# Board-A_Schematics.net
KiCad netlist of a schematic drawn in Altium Designer
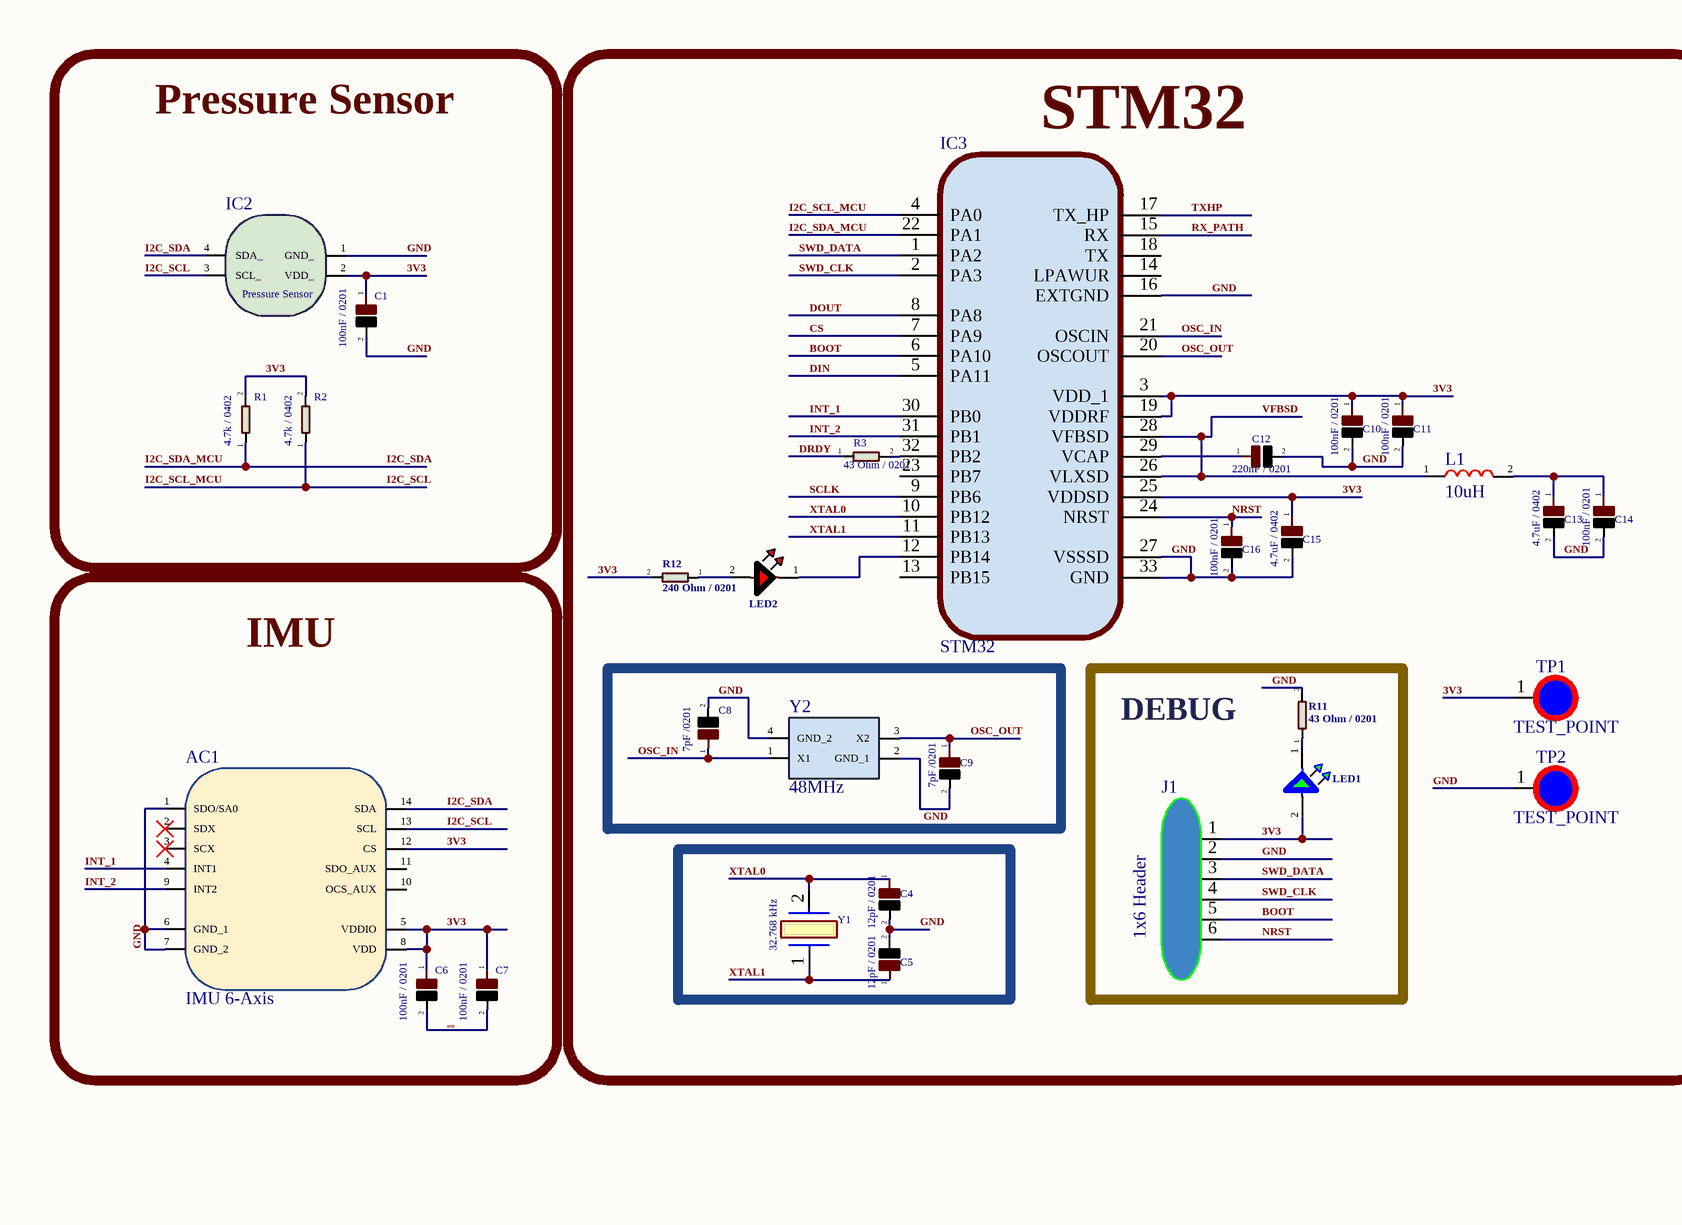
[diagram p0: Board-A_Schematics.SchDoc, left]
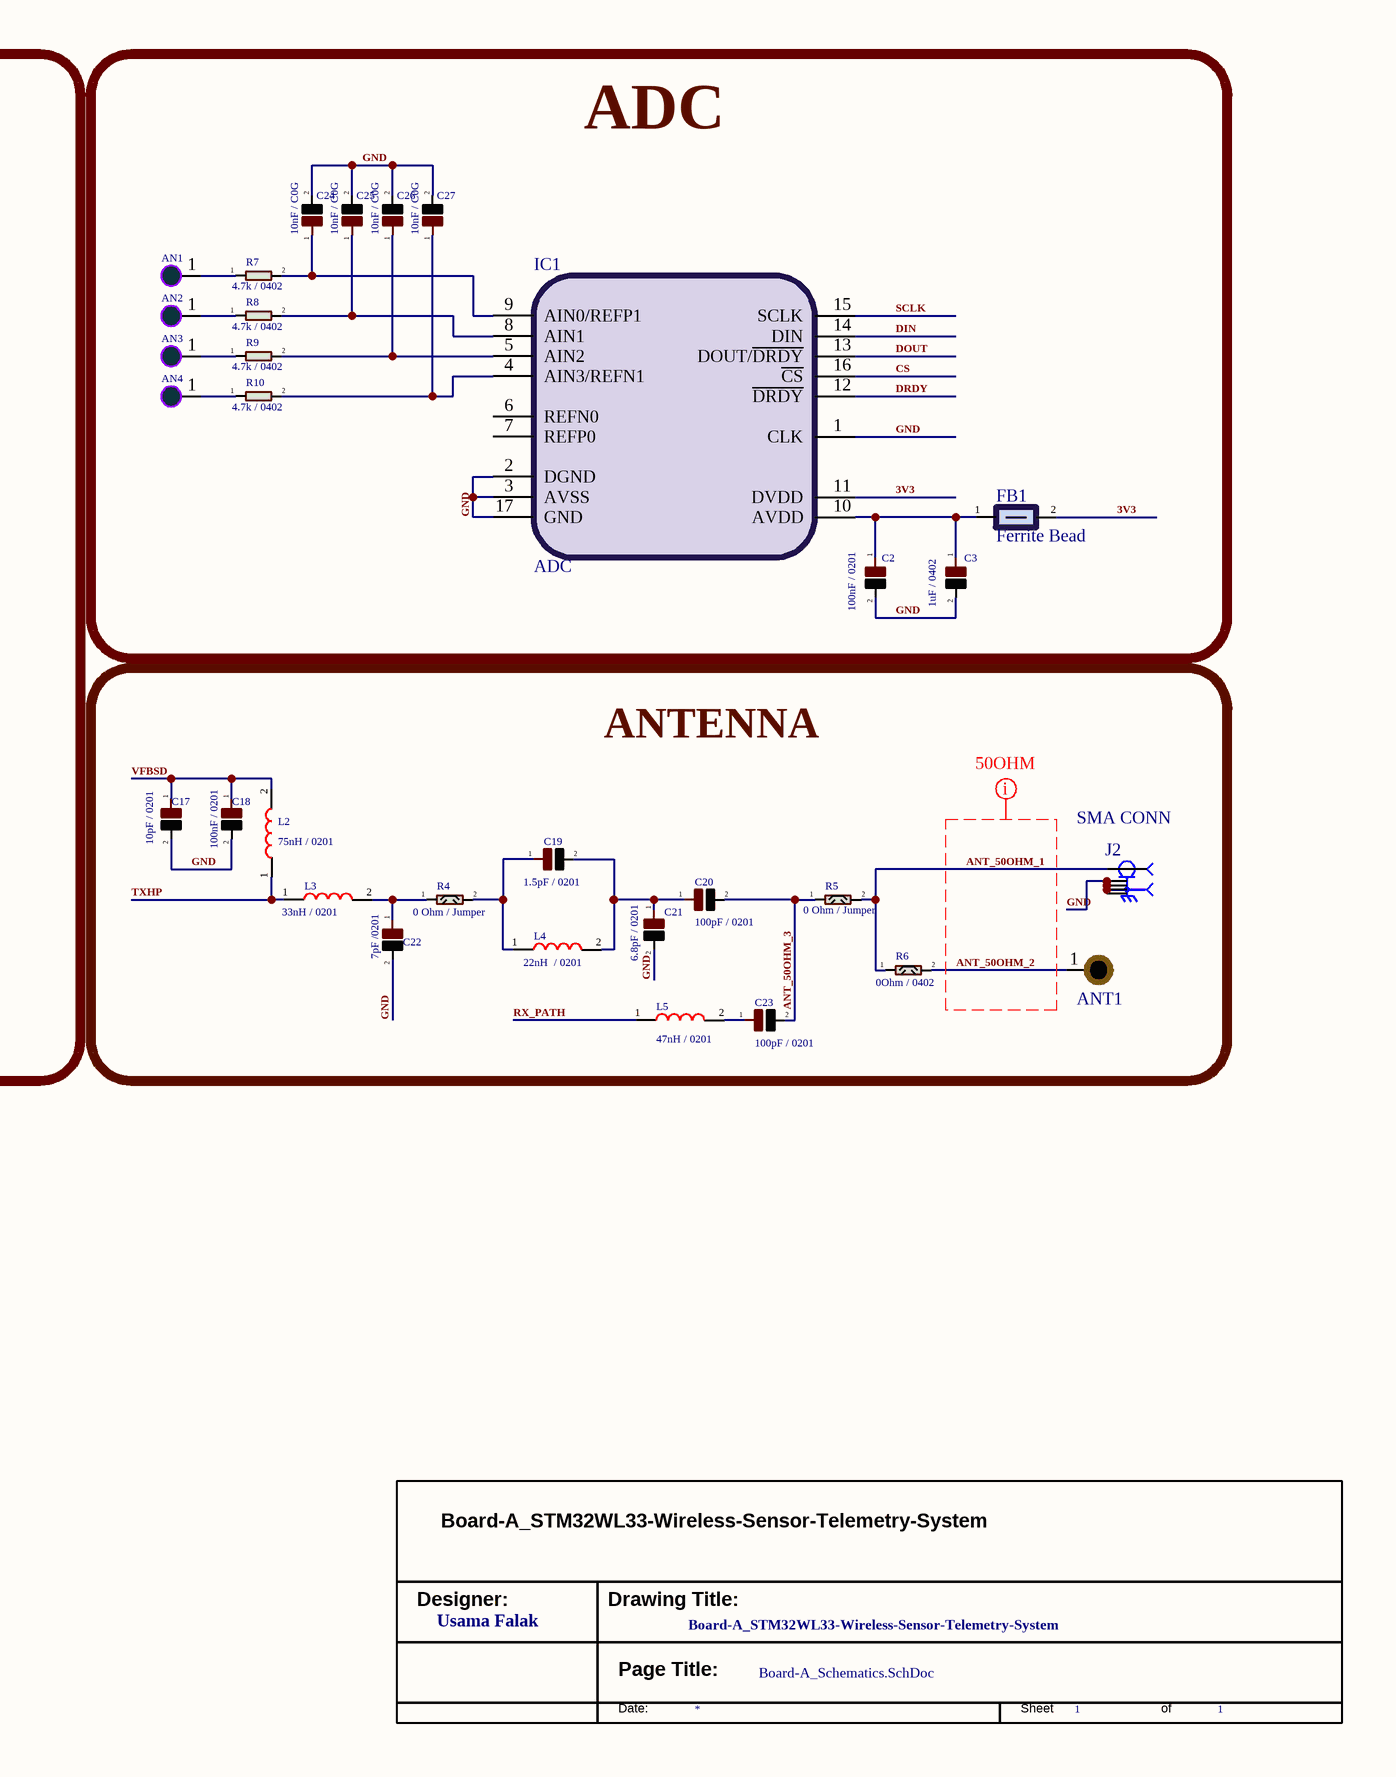
[diagram p1: Board-A_Schematics.SchDoc, right]

(export (version "E")
  (design (tool "Eeschema 10.0.6"))
  (components
    (comp (ref "*") (value "TitleBlock_MCPG_a") (libsource (lib "Sensor-SCHLIB") (part "TitleBlock_MCPG_a")))
    (comp (ref "AC1")
      (value "IMU 6-Axis")
      (footprint "Sensor-PCBLIB:LSM6DS3USTR")
      (description "Accelerometer, Gyroscope, 6 Axis Sensor I2C, SPI Output")
      (fields
        (field (name "MANUFACTURER_PART_NUMBER") "LSM6DSOTR")
        (field (name "MOUSER PART NUMBER") "511-LSM6DSOTR")
      )
      (libsource (lib "Sensor-SCHLIB") (part "LSM6DSOTR"))
    )
    (comp (ref "AN1")
      (value "ADC_AIN")
      (footprint "Analogue Pad")
      (libsource (lib "Sensor-SCHLIB") (part "ADC_PAD"))
    )
    (comp (ref "AN2")
      (value "ADC_AIN")
      (footprint "Analogue Pad")
      (libsource (lib "Sensor-SCHLIB") (part "ADC_PAD"))
    )
    (comp (ref "AN3")
      (value "ADC_AIN")
      (footprint "Analogue Pad")
      (libsource (lib "Sensor-SCHLIB") (part "ADC_PAD"))
    )
    (comp (ref "AN4")
      (value "ADC_AIN")
      (footprint "Analogue Pad")
      (libsource (lib "Sensor-SCHLIB") (part "ADC_PAD"))
    )
    (comp (ref "ANT1")
      (value "PAD")
      (footprint "ANTENNA-PAD")
      (libsource (lib "Sensor-SCHLIB") (part "ANTENNA-PAD"))
    )
    (comp (ref "C1")
      (value "100nF / 0201")
      (footprint "Sensor-PCBLIB:CAPC-C0201")
      (description "Multilayer Ceramic Capacitors MLCC - SMD/SMT 0.1 uF 16 VDC 10% 0201 X7R")
      (fields
        (field (name "MANUFACTURER_PART_NUMBER") "GRM033Z71C104KE14J")
        (field (name "MOUSER PART NUMBER") "81-GRM033Z71C104KE4J")
      )
      (libsource (lib "Sensor-SCHLIB") (part "GRM033Z71C104KE14J"))
    )
    (comp (ref "C2")
      (value "100nF / 0201")
      (footprint "Sensor-PCBLIB:CAPC-C0201")
      (description "Multilayer Ceramic Capacitors MLCC - SMD/SMT 0.1 uF 16 VDC 10% 0201 X7R")
      (fields
        (field (name "MANUFACTURER_PART_NUMBER") "GRM033Z71C104KE14J")
        (field (name "MOUSER PART NUMBER") "81-GRM033Z71C104KE4J")
      )
      (libsource (lib "Sensor-SCHLIB") (part "GRM033Z71C104KE14J"))
    )
    (comp (ref "C3")
      (value "1uF / 0402")
      (footprint "Sensor-PCBLIB:CAPC-C0402")
      (description "1uF ±10% 25V Ceramic Capacitor X6S 0402")
      (fields
        (field (name "MANUFACTURER_PART_NUMBER") "TMK105AC6105KV-F")
        (field (name "MOUSER PART NUMBER") "963-TMK105AC6105KV-F")
      )
      (libsource (lib "Sensor-SCHLIB") (part "TMK105AC6105KV-F"))
    )
    (comp (ref "C4")
      (value "12pF / 0201")
      (footprint "Sensor-PCBLIB:CAPC-C0201")
      (description "12pF ±2% 25V Ceramic Capacitor X6S 0201")
      (fields
        (field (name "MANUFACTURER_PART_NUMBER") "GJM0335C1E120GB01D")
        (field (name "MOUSER PART NUMBER") "81-GJM0335C1E120GB1D")
      )
      (libsource (lib "Sensor-SCHLIB") (part "GJM0335C1E120GB01D"))
    )
    (comp (ref "C5")
      (value "12pF / 0201")
      (footprint "Sensor-PCBLIB:CAPC-C0201")
      (description "12pF ±2% 25V Ceramic Capacitor X6S 0201")
      (fields
        (field (name "MANUFACTURER_PART_NUMBER") "GJM0335C1E120GB01D")
        (field (name "MOUSER PART NUMBER") "81-GJM0335C1E120GB1D")
      )
      (libsource (lib "") (part "GJM0335C1E120GB01D_1"))
    )
    (comp (ref "C6")
      (value "100nF / 0201")
      (footprint "Sensor-PCBLIB:CAPC-C0201")
      (description "Multilayer Ceramic Capacitors MLCC - SMD/SMT 0.1 uF 16 VDC 10% 0201 X7R")
      (fields
        (field (name "MANUFACTURER_PART_NUMBER") "GRM033Z71C104KE14J")
        (field (name "MOUSER PART NUMBER") "81-GRM033Z71C104KE4J")
      )
      (libsource (lib "Sensor-SCHLIB") (part "GRM033Z71C104KE14J"))
    )
    (comp (ref "C7")
      (value "100nF / 0201")
      (footprint "Sensor-PCBLIB:CAPC-C0201")
      (description "Multilayer Ceramic Capacitors MLCC - SMD/SMT 0.1 uF 16 VDC 10% 0201 X7R")
      (fields
        (field (name "MANUFACTURER_PART_NUMBER") "GRM033Z71C104KE14J")
        (field (name "MOUSER PART NUMBER") "81-GRM033Z71C104KE4J")
      )
      (libsource (lib "Sensor-SCHLIB") (part "GRM033Z71C104KE14J"))
    )
    (comp (ref "C8")
      (value "7pF /0201")
      (footprint "Sensor-PCBLIB:CAPC-C0201")
      (description "7pF 25V Ceramic Capacitor C0G 0201")
      (fields
        (field (name "MANUFACTURER_PART_NUMBER") "GJM0335C1E7R0BB01D")
        (field (name "LCSC-PART#") "C1864565")
      )
      (libsource (lib "Sensor-SCHLIB") (part "GJM0335C1E7R0BB01D"))
    )
    (comp (ref "C9")
      (value "7pF /0201")
      (footprint "Sensor-PCBLIB:CAPC-C0201")
      (description "7pF 25V Ceramic Capacitor C0G 0201")
      (fields
        (field (name "MANUFACTURER_PART_NUMBER") "GJM0335C1E7R0BB01D")
        (field (name "LCSC-PART#") "C1864565")
      )
      (libsource (lib "") (part "GJM0335C1E7R0BB01D_1"))
    )
    (comp (ref "C10")
      (value "100nF / 0201")
      (footprint "Sensor-PCBLIB:CAPC-C0201")
      (description "Multilayer Ceramic Capacitors MLCC - SMD/SMT 0.1 uF 16 VDC 10% 0201 X7R")
      (fields
        (field (name "MANUFACTURER_PART_NUMBER") "GRM033Z71C104KE14J")
        (field (name "MOUSER PART NUMBER") "81-GRM033Z71C104KE4J")
      )
      (libsource (lib "Sensor-SCHLIB") (part "GRM033Z71C104KE14J"))
    )
    (comp (ref "C11")
      (value "100nF / 0201")
      (footprint "Sensor-PCBLIB:CAPC-C0201")
      (description "Multilayer Ceramic Capacitors MLCC - SMD/SMT 0.1 uF 16 VDC 10% 0201 X7R")
      (fields
        (field (name "MANUFACTURER_PART_NUMBER") "GRM033Z71C104KE14J")
        (field (name "MOUSER PART NUMBER") "81-GRM033Z71C104KE4J")
      )
      (libsource (lib "Sensor-SCHLIB") (part "GRM033Z71C104KE14J"))
    )
    (comp (ref "C12")
      (value "220nF / 0201")
      (footprint "Sensor-PCBLIB:CAPC-C0201")
      (description "220nF X6S ±10% 10V 0201 Ceramic Capacitors RoHS")
      (fields
        (field (name "MANUFACTURER_PART_NUMBER") "GRM033C81A224KE01D")
        (field (name "LCSC-PART#") "C20044506")
      )
      (libsource (lib "Sensor-SCHLIB") (part "GRM033C81A224KE01D"))
    )
    (comp (ref "C13")
      (value "4.7uF / 0402")
      (footprint "Sensor-PCBLIB:CAPC-C0402")
      (description "4.7uF ±20% 25V Ceramic Capacitor 0402")
      (fields
        (field (name "MANUFACTURER_PART_NUMBER") "GRM155C61E475ME15J")
        (field (name "MOUSER PART NUMBER") "81-GRM15C61E475ME15J")
      )
      (libsource (lib "Sensor-SCHLIB") (part "GRM155C61E475ME15J"))
    )
    (comp (ref "C14")
      (value "100nF / 0201")
      (footprint "Sensor-PCBLIB:CAPC-C0201")
      (description "Multilayer Ceramic Capacitors MLCC - SMD/SMT 0.1 uF 16 VDC 10% 0201 X7R")
      (fields
        (field (name "MANUFACTURER_PART_NUMBER") "GRM033Z71C104KE14J")
        (field (name "MOUSER PART NUMBER") "81-GRM033Z71C104KE4J")
      )
      (libsource (lib "Sensor-SCHLIB") (part "GRM033Z71C104KE14J"))
    )
    (comp (ref "C15")
      (value "4.7uF / 0402")
      (footprint "Sensor-PCBLIB:CAPC-C0402")
      (description "4.7uF ±20% 25V Ceramic Capacitor 0402")
      (fields
        (field (name "MANUFACTURER_PART_NUMBER") "GRM155C61E475ME15J")
        (field (name "MOUSER PART NUMBER") "81-GRM15C61E475ME15J")
      )
      (libsource (lib "Sensor-SCHLIB") (part "GRM155C61E475ME15J"))
    )
    (comp (ref "C16")
      (value "100nF / 0201")
      (footprint "Sensor-PCBLIB:CAPC-C0201")
      (description "Multilayer Ceramic Capacitors MLCC - SMD/SMT 0.1 uF 16 VDC 10% 0201 X7R")
      (fields
        (field (name "MANUFACTURER_PART_NUMBER") "GRM033Z71C104KE14J")
        (field (name "MOUSER PART NUMBER") "81-GRM033Z71C104KE4J")
      )
      (libsource (lib "Sensor-SCHLIB") (part "GRM033Z71C104KE14J"))
    )
    (comp (ref "C17")
      (value "10pF / 0201")
      (footprint "Sensor-PCBLIB:CAPC-C0201")
      (description "10pF ±2% 25V Ceramic Capacitor C0G 0201")
      (fields
        (field (name "MANUFACTURER_PART_NUMBER") "GJM0335C1E100GB01D")
        (field (name "MOUSER PART NUMBER") "81-GJM0335C1E100GB1D")
      )
      (libsource (lib "Sensor-SCHLIB") (part "GJM0335C1E100GB01D"))
    )
    (comp (ref "C18")
      (value "100nF / 0201")
      (footprint "Sensor-PCBLIB:CAPC-C0201")
      (description "Multilayer Ceramic Capacitors MLCC - SMD/SMT 0.1 uF 16 VDC 10% 0201 X7R")
      (fields
        (field (name "MANUFACTURER_PART_NUMBER") "GRM033Z71C104KE14J")
        (field (name "MOUSER PART NUMBER") "81-GRM033Z71C104KE4J")
      )
      (libsource (lib "Sensor-SCHLIB") (part "GRM033Z71C104KE14J"))
    )
    (comp (ref "C19")
      (value "1.5pF / 0201")
      (footprint "Sensor-PCBLIB:CAPC-C0201")
      (description "1.5pF 25V Ceramic Capacitor C0G 0201")
      (fields
        (field (name "MANUFACTURER_PART_NUMBER") "GJM0335C1E1R5WB01D")
        (field (name "MOUSER PART NUMBER") "81-GJM0335C1E1R5WB1D")
      )
      (libsource (lib "Sensor-SCHLIB") (part "GJM0335C1E1R5WB01D"))
    )
    (comp (ref "C20")
      (value "100pF / 0201")
      (footprint "Sensor-PCBLIB:CAPC-C0201")
      (description "Multilayer Ceramic Capacitors MLCC - SMD/SMT 100 pF 25 VDC 1% 0201 C0G (NP0)")
      (fields
        (field (name "MANUFACTURER_PART_NUMBER") "GRM0335C1E101FA01D")
        (field (name "MOUSER PART NUMBER") "81-GRM0335C1E101FA1D")
      )
      (libsource (lib "Sensor-SCHLIB") (part "GRM0335C1E101FA01D"))
    )
    (comp (ref "C21")
      (value "6.8pF / 0201")
      (footprint "Sensor-PCBLIB:CAPC-C0201")
      (description "Multilayer Ceramic Capacitors MLCC - SMD/SMT 6.8 pF 25 VDC 0.25 pF 0201 C0G (NP0)")
      (fields
        (field (name "MANUFACTURER_PART_NUMBER") "GJM0335C1E6R8CB01D")
        (field (name "LCSC-PART#") "C415404")
      )
      (libsource (lib "Sensor-SCHLIB") (part "GJM0335C1E6R8CB01D"))
    )
    (comp (ref "C22")
      (value "7pF /0201")
      (footprint "Sensor-PCBLIB:CAPC-C0201")
      (description "7pF 25V Ceramic Capacitor C0G 0201")
      (fields
        (field (name "MANUFACTURER_PART_NUMBER") "GJM0335C1E7R0BB01D")
        (field (name "LCSC-PART#") "C1864565")
      )
      (libsource (lib "") (part "GJM0335C1E7R0BB01D_1"))
    )
    (comp (ref "C23")
      (value "100pF / 0201")
      (footprint "Sensor-PCBLIB:CAPC-C0201")
      (description "Multilayer Ceramic Capacitors MLCC - SMD/SMT 100 pF 25 VDC 1% 0201 C0G (NP0)")
      (fields
        (field (name "MANUFACTURER_PART_NUMBER") "GRM0335C1E101FA01D")
        (field (name "MOUSER PART NUMBER") "81-GRM0335C1E101FA1D")
      )
      (libsource (lib "Sensor-SCHLIB") (part "GRM0335C1E101FA01D"))
    )
    (comp (ref "C24")
      (value "10nF / C0G")
      (footprint "Sensor-PCBLIB:CAPC-C0402")
      (description "10nF ±2% 25V Ceramic Capacitor C0G 0402")
      (fields
        (field (name "MANUFACTURER_PART_NUMBER") "GRM1555C1E103GE01D")
        (field (name "MOUSER PART NUMBER") "81-GRM1555C1E103GE1D")
      )
      (libsource (lib "Sensor-SCHLIB") (part "GRM1555C1E103GE01D"))
    )
    (comp (ref "C25")
      (value "10nF / C0G")
      (footprint "Sensor-PCBLIB:CAPC-C0402")
      (description "10nF ±2% 25V Ceramic Capacitor C0G 0402")
      (fields
        (field (name "MANUFACTURER_PART_NUMBER") "GRM1555C1E103GE01D")
        (field (name "MOUSER PART NUMBER") "81-GRM1555C1E103GE1D")
      )
      (libsource (lib "Sensor-SCHLIB") (part "GRM1555C1E103GE01D"))
    )
    (comp (ref "C26")
      (value "10nF / C0G")
      (footprint "Sensor-PCBLIB:CAPC-C0402")
      (description "10nF ±2% 25V Ceramic Capacitor C0G 0402")
      (fields
        (field (name "MANUFACTURER_PART_NUMBER") "GRM1555C1E103GE01D")
        (field (name "MOUSER PART NUMBER") "81-GRM1555C1E103GE1D")
      )
      (libsource (lib "Sensor-SCHLIB") (part "GRM1555C1E103GE01D"))
    )
    (comp (ref "C27")
      (value "10nF / C0G")
      (footprint "Sensor-PCBLIB:CAPC-C0402")
      (description "10nF ±2% 25V Ceramic Capacitor C0G 0402")
      (fields
        (field (name "MANUFACTURER_PART_NUMBER") "GRM1555C1E103GE01D")
        (field (name "MOUSER PART NUMBER") "81-GRM1555C1E103GE1D")
      )
      (libsource (lib "Sensor-SCHLIB") (part "GRM1555C1E103GE01D"))
    )
    (comp (ref "FB1")
      (value "Ferrite Bead")
      (footprint "Sensor-PCBLIB:BLM15PX_BH1")
      (description "600Ω@100MHz Ferrite Bead 0402 900mA 230mΩ")
      (fields
        (field (name "MANUFACTURER_PART_NUMBER") "BLM15PX601SH1D")
        (field (name "MOUSER PART NUMBER") "81-BLM15PX601SH1D")
      )
      (libsource (lib "Sensor-SCHLIB") (part "BLM15PX601SH1D"))
    )
    (comp (ref "IC1")
      (value "ADC")
      (footprint "Sensor-PCBLIB:QFN50P350X350X100-17N-D")
      (description "24 Bit Analog to Digital Converter 2, 4 Input 1 Sigma-Delta 16-VQFN (3.5x3.5)")
      (fields
        (field (name "MANUFACTURER_PART_NUMBER") "ADS1220IRVAR")
        (field (name "MOUSER PART NUMBER") "595-ADS1220IRVAR")
      )
      (libsource (lib "Sensor-SCHLIB") (part "ADS1220IRVAR"))
    )
    (comp (ref "IC2")
      (value "Pressure Sensor")
      (footprint "Sensor-PCBLIB:MS584002BA01")
      (description "Pressure Sensor 4.35PSI ~ 17.4PSI (30kPa ~ 120kPa) Absolute 24 b 4-SMD, No Lead")
      (fields
        (field (name "MANUFACTURER_PART_NUMBER") "MS5840-02BA01")
        (field (name "MOUSER PART NUMBER") "824-MS5840-02BA01")
      )
      (libsource (lib "Sensor-SCHLIB") (part "MS5840-02BA01"))
    )
    (comp (ref "IC3")
      (value "STM32")
      (footprint "Sensor-PCBLIB:QFN50P500X500X100-33N-D")
      (fields (field (name "MANUFACTURER_PART_NUMBER") "STM32WL33KBV7"))
      (libsource (lib "Sensor-SCHLIB") (part "STM32WL33KBV7"))
    )
    (comp (ref "J1")
      (value "1x6 Header")
      (footprint "Sensor-PCBLIB:GRPB032MWCNRC")
      (description "Connector")
      (fields (field (name "MANUFACTURER_PART_NUMBER") "GRPB032MWCN-RC"))
      (libsource (lib "Sensor-SCHLIB") (part "GRPB032MWCN-RC"))
    )
    (comp (ref "J2")
      (value "SMA CONN")
      (footprint "SAMTEC_SMA-J-P-H-ST-EM1")
      (fields (field (name "MF") "Samtec") (field (name "MP") "SMA-J-P-H-ST-EM1"))
      (libsource (lib "Sensor-SCHLIB") (part "SMA-J-P-H-ST-EM1"))
    )
    (comp (ref "L1")
      (value "10uH")
      (footprint "Sensor-PCBLIB:IND-C1608X95N")
      (description "10uH 1.05Ω Standard AEC-Q200")
      (fields
        (field (name "MANUFACTURER_PART_NUMBER") "MLZ1608M100WTD25")
        (field (name "MOUSER PART NUMBER") "810-MLZ1608M100WTD25")
      )
      (libsource (lib "Sensor-SCHLIB") (part "MLZ1608M100WTD25"))
    )
    (comp (ref "L2")
      (value "75nH / 0201")
      (footprint "Sensor-PCBLIB:INDC-C0201")
      (description "100mA 75nH ±5% 10Ω 0201 Fixed Inductors RoHS")
      (fields
        (field (name "MANUFACTURER_PART_NUMBER") "LQP03TN75NJ02D")
        (field (name "MOUSER PART NUMBER") "81-LQP03TN75NJ02D")
      )
      (libsource (lib "Sensor-SCHLIB") (part "LQP03TN75NJ02D"))
    )
    (comp (ref "L3")
      (value "33nH / 0201")
      (footprint "Sensor-PCBLIB:INDC-C0201")
      (description "110mA 33nH ±5% 4.25Ω 0201 Fixed Inductors RoHS")
      (fields
        (field (name "MANUFACTURER_PART_NUMBER") "LQP03TG33NJ02D")
        (field (name "MOUSER PART NUMBER") "81-LQP03TG33NJ02D")
      )
      (libsource (lib "Sensor-SCHLIB") (part "LQP03TG33NJ02D"))
    )
    (comp (ref "L4")
      (value "22nH  / 0201")
      (footprint "Sensor-PCBLIB:INDC-C0201")
      (description "140mA 22nH ±5% 2.85Ω Thick Film Inductor 0201 Fixed Inductors RoHS")
      (fields
        (field (name "MANUFACTURER_PART_NUMBER") "LQP03TG22NJ02D")
        (field (name "MOUSER PART NUMBER") "81-LQP03TG22NJ02D")
      )
      (libsource (lib "Sensor-SCHLIB") (part "LQP03TG22NJ02D"))
    )
    (comp (ref "L5")
      (value "47nH / 0201")
      (footprint "Sensor-PCBLIB:IND-0201")
      (description "Inductor")
      (fields
        (field (name "MANUFACTURER_PART_NUMBER") "LQP03HQ47NH02D")
        (field (name "MOUSER PART NUMBER") "81-LQP03HQ47NH02D")
      )
      (libsource (lib "Sensor-SCHLIB") (part "LQP03HQ47NH02D"))
    )
    (comp (ref "LED1")
      (value "GREEN-LED")
      (footprint "Sensor-PCBLIB:LEDC-C0201")
      (description "Emerald Green 525nm LED Indication - Discrete 3.3V 0201")
      (fields (field (name "MANUFACTURER_PART_NUMBER") "XL-0201UGC"))
      (libsource (lib "Sensor-SCHLIB") (part "XL-0201UGC"))
    )
    (comp (ref "LED2")
      (value "RED-LED")
      (footprint "Sensor-PCBLIB:LEDC-C0201")
      (description "Red LED Indication - Discrete 0201")
      (fields (field (name "MANUFACTURER_PART_NUMBER") "XL-0201SURC") (field (name "LCSC-PART#") "C3646923"))
      (libsource (lib "Sensor-SCHLIB") (part "XL-0201SURC"))
    )
    (comp (ref "R1")
      (value "4.7k / 0402")
      (footprint "Sensor-PCBLIB:RESC-C0402")
      (description "62.5mW 4.7kΩ 50V Thin Film Resistor ±25ppm/℃ ±0.1% 0402 Chip Resistor - Surface Mount RoHS")
      (fields
        (field (name "MANUFACTURER_PART_NUMBER") "RT0402BRD074K7L")
        (field (name "MOUSER PART NUMBER") "603-RT0402BRD074K7L")
      )
      (libsource (lib "") (part "RT0402BRD074K7L_1"))
    )
    (comp (ref "R2")
      (value "4.7k / 0402")
      (footprint "Sensor-PCBLIB:RESC-C0402")
      (description "62.5mW 4.7kΩ 50V Thin Film Resistor ±25ppm/℃ ±0.1% 0402 Chip Resistor - Surface Mount RoHS")
      (fields
        (field (name "MANUFACTURER_PART_NUMBER") "RT0402BRD074K7L")
        (field (name "MOUSER PART NUMBER") "603-RT0402BRD074K7L")
      )
      (libsource (lib "") (part "RT0402BRD074K7L_1"))
    )
    (comp (ref "R3")
      (value "43 Ohm / 0201")
      (footprint "RESC-C0201")
      (description "43Ω ±1% 50mW 0201 Thick Film")
      (fields (field (name "LCSC-PART#") "C226550"))
      (libsource (lib "") (part "AC0201FR-0743RL_1"))
    )
    (comp (ref "R4")
      (value "0 Ohm / Jumper")
      (footprint "Sensor-PCBLIB:RESC-C0201")
      (description "Resistor")
      (fields
        (field (name "MANUFACTURER_PART_NUMBER") "CRCW02010000Z0ED")
        (field (name "MOUSER PART NUMBER") "71-CRCW02010000Z0ED")
      )
      (libsource (lib "Sensor-SCHLIB") (part "CRCW02010000Z0ED"))
    )
    (comp (ref "R5")
      (value "0 Ohm / Jumper")
      (footprint "Sensor-PCBLIB:RESC-C0201")
      (description "Resistor")
      (fields
        (field (name "MANUFACTURER_PART_NUMBER") "CRCW02010000Z0ED")
        (field (name "MOUSER PART NUMBER") "71-CRCW02010000Z0ED")
      )
      (libsource (lib "Sensor-SCHLIB") (part "CRCW02010000Z0ED"))
    )
    (comp (ref "R6")
      (value "0Ohm / 0402")
      (footprint "Sensor-PCBLIB:RESC-C0402")
      (description "0 Ohms Jumper Chip Resistor 0402 (1005 Metric) Automotive AEC-Q200 Thick Film")
      (fields
        (field (name "MANUFACTURER_PART_NUMBER") "ERJ-2GE0R00X")
        (field (name "MOUSER PART NUMBER") "667-ERJ-2GE0R00X")
      )
      (libsource (lib "Sensor-SCHLIB") (part "ERJ-2GE0R00X"))
    )
    (comp (ref "R7")
      (value "4.7k / 0402")
      (footprint "Sensor-PCBLIB:RESC-C0402")
      (description "62.5mW 4.7kΩ 50V Thin Film Resistor ±25ppm/℃ ±0.1% 0402 Chip Resistor - Surface Mount RoHS")
      (fields
        (field (name "MANUFACTURER_PART_NUMBER") "RT0402BRD074K7L")
        (field (name "MOUSER PART NUMBER") "603-RT0402BRD074K7L")
      )
      (libsource (lib "Sensor-SCHLIB") (part "RT0402BRD074K7L"))
    )
    (comp (ref "R8")
      (value "4.7k / 0402")
      (footprint "Sensor-PCBLIB:RESC-C0402")
      (description "62.5mW 4.7kΩ 50V Thin Film Resistor ±25ppm/℃ ±0.1% 0402 Chip Resistor - Surface Mount RoHS")
      (fields
        (field (name "MANUFACTURER_PART_NUMBER") "RT0402BRD074K7L")
        (field (name "MOUSER PART NUMBER") "603-RT0402BRD074K7L")
      )
      (libsource (lib "Sensor-SCHLIB") (part "RT0402BRD074K7L"))
    )
    (comp (ref "R9")
      (value "4.7k / 0402")
      (footprint "Sensor-PCBLIB:RESC-C0402")
      (description "62.5mW 4.7kΩ 50V Thin Film Resistor ±25ppm/℃ ±0.1% 0402 Chip Resistor - Surface Mount RoHS")
      (fields
        (field (name "MANUFACTURER_PART_NUMBER") "RT0402BRD074K7L")
        (field (name "MOUSER PART NUMBER") "603-RT0402BRD074K7L")
      )
      (libsource (lib "Sensor-SCHLIB") (part "RT0402BRD074K7L"))
    )
    (comp (ref "R10")
      (value "4.7k / 0402")
      (footprint "Sensor-PCBLIB:RESC-C0402")
      (description "62.5mW 4.7kΩ 50V Thin Film Resistor ±25ppm/℃ ±0.1% 0402 Chip Resistor - Surface Mount RoHS")
      (fields
        (field (name "MANUFACTURER_PART_NUMBER") "RT0402BRD074K7L")
        (field (name "MOUSER PART NUMBER") "603-RT0402BRD074K7L")
      )
      (libsource (lib "Sensor-SCHLIB") (part "RT0402BRD074K7L"))
    )
    (comp (ref "R11")
      (value "43 Ohm / 0201")
      (footprint "RESC-C0201")
      (description "43Ω ±1% 50mW 0201 Thick Film")
      (fields (field (name "LCSC-PART#") "C226550"))
      (libsource (lib "Sensor-SCHLIB") (part "AC0201FR-0743RL"))
    )
    (comp (ref "R12")
      (value "240 Ohm / 0201")
      (footprint "RESC-C0201")
      (description "50mW 240Ω 25V Thick Film Resistor ±1% ±200ppm/℃ 0201 Chip Resistor - Surface Mount RoHS")
      (fields (field (name "LCSC-PART#") "C226476"))
      (libsource (lib "Sensor-SCHLIB") (part "AC0201FR-07240RL"))
    )
    (comp (ref "TP1")
      (value "TEST_POINT")
      (footprint "TEST-POINT")
      (libsource (lib "Sensor-SCHLIB") (part "TEST_POINT"))
    )
    (comp (ref "TP2")
      (value "TEST_POINT")
      (footprint "TEST-POINT")
      (libsource (lib "Sensor-SCHLIB") (part "TEST_POINT"))
    )
    (comp (ref "Y1")
      (value "32.768 kHz")
      (footprint "Sensor-PCBLIB:Q13FC1350000400")
      (description "32.768 kHz ±20ppm Crystal 12.5pF 70 kOhms 2-SMD, No Lead")
      (fields
        (field (name "MANUFACTURER_PART_NUMBER") "Q13FC1350000400")
        (field (name "LCSC-PART#") "C32346")
      )
      (libsource (lib "Sensor-SCHLIB") (part "Q13FC1350000400"))
    )
    (comp (ref "Y2")
      (value "48MHz")
      (footprint "Sensor-PCBLIB:ABM11W300000MHZ4B1UT3")
      (description "Crystal 48MHz ±10ppm 7pF 40Ω SMD2016-4P")
      (fields
        (field (name "MANUFACTURER_PART_NUMBER") "ABM11W-48.0000MHZ-7-B1U-T3")
        (field (name "MOUSER PART NUMBER") "815-11W48-7B1UT")
      )
      (libsource (lib "Sensor-SCHLIB") (part "ABM11W-48.0000MHZ-7-B1U-T3"))
    )
  )
  (nets
    (net (code "1") (name "/3V3") (class "Default")
      (node (ref "AC1") (pin "12") (pinfunction "CS_12") (pintype "passive"))
      (node (ref "AC1") (pin "5") (pinfunction "VDDIO_5") (pintype "passive"))
      (node (ref "AC1") (pin "8") (pinfunction "VDD_8") (pintype "passive"))
      (node (ref "C1") (pin "1") (pinfunction "1_1") (pintype "passive"))
      (node (ref "C10") (pin "1") (pinfunction "1_1") (pintype "passive"))
      (node (ref "C11") (pin "1") (pinfunction "1_1") (pintype "passive"))
      (node (ref "C15") (pin "1") (pinfunction "1_1") (pintype "passive"))
      (node (ref "C6") (pin "1") (pinfunction "1_1") (pintype "passive"))
      (node (ref "C7") (pin "1") (pinfunction "1_1") (pintype "passive"))
      (node (ref "FB1") (pin "2") (pinfunction "2_2") (pintype "passive"))
      (node (ref "IC1") (pin "11") (pinfunction "DVDD_11") (pintype "passive"))
      (node (ref "IC2") (pin "2") (pinfunction "VDD__2") (pintype "passive"))
      (node (ref "IC3") (pin "19") (pinfunction "VDDRF_19") (pintype "passive"))
      (node (ref "IC3") (pin "25") (pinfunction "VDDSD_25") (pintype "passive"))
      (node (ref "IC3") (pin "3") (pinfunction "VDD_1_3") (pintype "passive"))
      (node (ref "J1") (pin "1") (pinfunction "1_1") (pintype "passive"))
      (node (ref "LED1") (pin "2") (pinfunction "A_2") (pintype "passive"))
      (node (ref "R1") (pin "2") (pinfunction "2_2") (pintype "passive"))
      (node (ref "R12") (pin "2") (pinfunction "2_2") (pintype "passive"))
      (node (ref "R2") (pin "2") (pinfunction "2_2") (pintype "passive"))
      (node (ref "TP1") (pin "1") (pinfunction "1_1") (pintype "passive"))
    )
    (net (code "2") (name "/ANT_50OHM_1") (class "Default")
      (node (ref "J2") (pin "1") (pinfunction "1_1") (pintype "passive"))
      (node (ref "R5") (pin "2") (pinfunction "2_2") (pintype "passive"))
      (node (ref "R6") (pin "1") (pinfunction "1_1") (pintype "passive"))
    )
    (net (code "3") (name "/ANT_50OHM_2") (class "Default")
      (node (ref "ANT1") (pin "1") (pinfunction "0_1") (pintype "passive"))
      (node (ref "R6") (pin "2") (pinfunction "2_2") (pintype "passive"))
    )
    (net (code "4") (name "/ANT_50OHM_3") (class "Default")
      (node (ref "C20") (pin "2") (pinfunction "2_2") (pintype "passive"))
      (node (ref "C23") (pin "2") (pinfunction "2_2") (pintype "passive"))
      (node (ref "R5") (pin "1") (pinfunction "1_1") (pintype "passive"))
    )
    (net (code "5") (name "/BOOT") (class "Default")
      (node (ref "IC3") (pin "6") (pinfunction "PA10_6") (pintype "passive"))
      (node (ref "J1") (pin "5") (pinfunction "5_5") (pintype "passive"))
    )
    (net (code "6") (name "/CS") (class "Default")
      (node (ref "IC1") (pin "16") (pinfunction "~{CS}_16") (pintype "passive"))
      (node (ref "IC3") (pin "7") (pinfunction "PA9_7") (pintype "passive"))
    )
    (net (code "7") (name "/DIN") (class "Default")
      (node (ref "IC1") (pin "14") (pinfunction "DIN_14") (pintype "passive"))
      (node (ref "IC3") (pin "5") (pinfunction "PA11_5") (pintype "passive"))
    )
    (net (code "8") (name "/DOUT") (class "Default")
      (node (ref "IC1") (pin "13") (pinfunction "DOUT/~{DRDY}_13") (pintype "passive"))
      (node (ref "IC3") (pin "8") (pinfunction "PA8_8") (pintype "passive"))
    )
    (net (code "9") (name "/DRDY") (class "Default")
      (node (ref "IC1") (pin "12") (pinfunction "~{DRDY}_12") (pintype "passive"))
      (node (ref "R3") (pin "1") (pinfunction "1_1") (pintype "passive"))
    )
    (net (code "10") (name "/GND") (class "Default")
      (node (ref "AC1") (pin "1") (pinfunction "SDO/SA0_1") (pintype "passive"))
      (node (ref "AC1") (pin "6") (pinfunction "GND_1_6") (pintype "passive"))
      (node (ref "AC1") (pin "7") (pinfunction "GND_2_7") (pintype "passive"))
      (node (ref "C1") (pin "2") (pinfunction "2_2") (pintype "passive"))
      (node (ref "C10") (pin "2") (pinfunction "2_2") (pintype "passive"))
      (node (ref "C11") (pin "2") (pinfunction "2_2") (pintype "passive"))
      (node (ref "C12") (pin "2") (pinfunction "2_2") (pintype "passive"))
      (node (ref "C13") (pin "2") (pinfunction "2_2") (pintype "passive"))
      (node (ref "C14") (pin "2") (pinfunction "2_2") (pintype "passive"))
      (node (ref "C15") (pin "2") (pinfunction "2_2") (pintype "passive"))
      (node (ref "C16") (pin "2") (pinfunction "2_2") (pintype "passive"))
      (node (ref "C17") (pin "2") (pinfunction "2_2") (pintype "passive"))
      (node (ref "C18") (pin "2") (pinfunction "2_2") (pintype "passive"))
      (node (ref "C2") (pin "2") (pinfunction "2_2") (pintype "passive"))
      (node (ref "C21") (pin "2") (pinfunction "2_2") (pintype "passive"))
      (node (ref "C22") (pin "2") (pinfunction "2_2") (pintype "passive"))
      (node (ref "C24") (pin "2") (pinfunction "2_2") (pintype "passive"))
      (node (ref "C25") (pin "2") (pinfunction "2_2") (pintype "passive"))
      (node (ref "C26") (pin "2") (pinfunction "2_2") (pintype "passive"))
      (node (ref "C27") (pin "2") (pinfunction "2_2") (pintype "passive"))
      (node (ref "C3") (pin "2") (pinfunction "2_2") (pintype "passive"))
      (node (ref "C4") (pin "2") (pinfunction "2_2") (pintype "passive"))
      (node (ref "C5") (pin "2") (pinfunction "2_2") (pintype "passive"))
      (node (ref "C6") (pin "2") (pinfunction "2_2") (pintype "passive"))
      (node (ref "C7") (pin "2") (pinfunction "2_2") (pintype "passive"))
      (node (ref "C8") (pin "2") (pinfunction "2_2") (pintype "passive"))
      (node (ref "C9") (pin "2") (pinfunction "2_2") (pintype "passive"))
      (node (ref "IC1") (pin "1") (pinfunction "CLK_1") (pintype "passive"))
      (node (ref "IC1") (pin "17") (pinfunction "GND_17") (pintype "passive"))
      (node (ref "IC1") (pin "2") (pinfunction "DGND_2") (pintype "passive"))
      (node (ref "IC1") (pin "3") (pinfunction "AVSS_3") (pintype "passive"))
      (node (ref "IC2") (pin "1") (pinfunction "GND__1") (pintype "passive"))
      (node (ref "IC3") (pin "16") (pinfunction "EXTGND_16") (pintype "passive"))
      (node (ref "IC3") (pin "27") (pinfunction "VSSSD_27") (pintype "passive"))
      (node (ref "IC3") (pin "33") (pinfunction "GND_33") (pintype "passive"))
      (node (ref "J1") (pin "2") (pinfunction "2_2") (pintype "passive"))
      (node (ref "J2") (pin "2_1") (pinfunction "2_2_1") (pintype "passive"))
      (node (ref "J2") (pin "2_2") (pinfunction "2_2_2") (pintype "passive"))
      (node (ref "J2") (pin "3_1") (pinfunction "2_3_1") (pintype "passive"))
      (node (ref "J2") (pin "3_2") (pinfunction "2_3_2") (pintype "passive"))
      (node (ref "R11") (pin "2") (pinfunction "2_2") (pintype "passive"))
      (node (ref "TP2") (pin "1") (pinfunction "1_1") (pintype "passive"))
      (node (ref "Y2") (pin "2") (pinfunction "GND_1_2") (pintype "passive"))
      (node (ref "Y2") (pin "4") (pinfunction "GND_2_4") (pintype "passive"))
    )
    (net (code "11") (name "/I2C_SCL") (class "Default")
      (node (ref "AC1") (pin "13") (pinfunction "SCL_13") (pintype "passive"))
      (node (ref "IC2") (pin "3") (pinfunction "SCL__3") (pintype "passive"))
      (node (ref "IC3") (pin "4") (pinfunction "PA0_4") (pintype "passive"))
      (node (ref "R2") (pin "1") (pinfunction "1_1") (pintype "passive"))
    )
    (net (code "12") (name "/I2C_SDA") (class "Default")
      (node (ref "AC1") (pin "14") (pinfunction "SDA_14") (pintype "passive"))
      (node (ref "IC2") (pin "4") (pinfunction "SDA__4") (pintype "passive"))
      (node (ref "IC3") (pin "22") (pinfunction "PA1_22") (pintype "passive"))
      (node (ref "R1") (pin "1") (pinfunction "1_1") (pintype "passive"))
    )
    (net (code "13") (name "/INT_1") (class "Default")
      (node (ref "AC1") (pin "4") (pinfunction "INT1_4") (pintype "passive"))
      (node (ref "IC3") (pin "30") (pinfunction "PB0_30") (pintype "passive"))
    )
    (net (code "14") (name "/INT_2") (class "Default")
      (node (ref "AC1") (pin "9") (pinfunction "INT2_9") (pintype "passive"))
      (node (ref "IC3") (pin "31") (pinfunction "PB1_31") (pintype "passive"))
    )
    (net (code "15") (name "/NRST") (class "Default")
      (node (ref "C16") (pin "1") (pinfunction "1_1") (pintype "passive"))
      (node (ref "IC3") (pin "24") (pinfunction "NRST_24") (pintype "passive"))
      (node (ref "J1") (pin "6") (pinfunction "6_6") (pintype "passive"))
    )
    (net (code "16") (name "/OSC_IN") (class "Default")
      (node (ref "C8") (pin "1") (pinfunction "1_1") (pintype "passive"))
      (node (ref "IC3") (pin "21") (pinfunction "OSCIN_21") (pintype "passive"))
      (node (ref "Y2") (pin "1") (pinfunction "X1_1") (pintype "passive"))
    )
    (net (code "17") (name "/OSC_OUT") (class "Default")
      (node (ref "C9") (pin "1") (pinfunction "1_1") (pintype "passive"))
      (node (ref "IC3") (pin "20") (pinfunction "OSCOUT_20") (pintype "passive"))
      (node (ref "Y2") (pin "3") (pinfunction "X2_3") (pintype "passive"))
    )
    (net (code "18") (name "/RX_PATH") (class "Default")
      (node (ref "IC3") (pin "15") (pinfunction "RX_15") (pintype "passive"))
      (node (ref "L5") (pin "1") (pinfunction "1_1") (pintype "passive"))
    )
    (net (code "19") (name "/SCLK") (class "Default")
      (node (ref "IC1") (pin "15") (pinfunction "SCLK_15") (pintype "passive"))
      (node (ref "IC3") (pin "9") (pinfunction "PB6_9") (pintype "passive"))
    )
    (net (code "20") (name "/SWD_CLK") (class "Default")
      (node (ref "IC3") (pin "2") (pinfunction "PA3_2") (pintype "passive"))
      (node (ref "J1") (pin "4") (pinfunction "4_4") (pintype "passive"))
    )
    (net (code "21") (name "/SWD_DATA") (class "Default")
      (node (ref "IC3") (pin "1") (pinfunction "PA2_1") (pintype "passive"))
      (node (ref "J1") (pin "3") (pinfunction "3_3") (pintype "passive"))
    )
    (net (code "22") (name "/TXHP") (class "Default")
      (node (ref "IC3") (pin "17") (pinfunction "TX_HP_17") (pintype "passive"))
      (node (ref "L2") (pin "1") (pinfunction "1_1") (pintype "passive"))
      (node (ref "L3") (pin "1") (pinfunction "1_1") (pintype "passive"))
    )
    (net (code "23") (name "/VFBSD") (class "Default")
      (node (ref "C17") (pin "1") (pinfunction "1_1") (pintype "passive"))
      (node (ref "C18") (pin "1") (pinfunction "1_1") (pintype "passive"))
      (node (ref "IC3") (pin "26") (pinfunction "VLXSD_26") (pintype "passive"))
      (node (ref "IC3") (pin "28") (pinfunction "VFBSD_28") (pintype "passive"))
      (node (ref "L1") (pin "1") (pinfunction "1_1") (pintype "passive"))
      (node (ref "L2") (pin "2") (pinfunction "2_2") (pintype "passive"))
    )
    (net (code "24") (name "/XTAL0") (class "Default")
      (node (ref "C4") (pin "1") (pinfunction "1_1") (pintype "passive"))
      (node (ref "IC3") (pin "10") (pinfunction "PB12_10") (pintype "passive"))
      (node (ref "Y1") (pin "2") (pinfunction "CRYSTAL_2_2") (pintype "passive"))
    )
    (net (code "25") (name "/XTAL1") (class "Default")
      (node (ref "C5") (pin "1") (pinfunction "1_1") (pintype "passive"))
      (node (ref "IC3") (pin "11") (pinfunction "PB13_11") (pintype "passive"))
      (node (ref "Y1") (pin "1") (pintype "passive"))
    )
    (net (code "26") (name "Net-(AN1-Pad1)") (class "Default")
      (node (ref "AN1") (pin "1") (pintype "passive"))
      (node (ref "R7") (pin "1") (pinfunction "1_1") (pintype "passive"))
    )
    (net (code "27") (name "Net-(AN2-Pad1)") (class "Default")
      (node (ref "AN2") (pin "1") (pintype "passive"))
      (node (ref "R8") (pin "1") (pinfunction "1_1") (pintype "passive"))
    )
    (net (code "28") (name "Net-(AN3-Pad1)") (class "Default")
      (node (ref "AN3") (pin "1") (pintype "passive"))
      (node (ref "R9") (pin "1") (pinfunction "1_1") (pintype "passive"))
    )
    (net (code "29") (name "Net-(AN4-Pad1)") (class "Default")
      (node (ref "AN4") (pin "1") (pintype "passive"))
      (node (ref "R10") (pin "1") (pinfunction "1_1") (pintype "passive"))
    )
    (net (code "30") (name "Net-(C13-Pad1)") (class "Default")
      (node (ref "C13") (pin "1") (pinfunction "1_1") (pintype "passive"))
      (node (ref "C14") (pin "1") (pinfunction "1_1") (pintype "passive"))
      (node (ref "L1") (pin "2") (pinfunction "2_2") (pintype "passive"))
    )
    (net (code "31") (name "Net-(C19-Pad1)") (class "Default")
      (node (ref "C19") (pin "1") (pinfunction "1_1") (pintype "passive"))
      (node (ref "L4") (pin "1") (pinfunction "1_1") (pintype "passive"))
      (node (ref "R4") (pin "2") (pinfunction "2_2") (pintype "passive"))
    )
    (net (code "32") (name "Net-(C19-Pad2)") (class "Default")
      (node (ref "C19") (pin "2") (pinfunction "2_2") (pintype "passive"))
      (node (ref "C20") (pin "1") (pinfunction "1_1") (pintype "passive"))
      (node (ref "C21") (pin "1") (pinfunction "1_1") (pintype "passive"))
      (node (ref "L4") (pin "2") (pinfunction "2_2") (pintype "passive"))
    )
    (net (code "33") (name "Net-(C22-Pad1)") (class "Default")
      (node (ref "C22") (pin "1") (pinfunction "1_1") (pintype "passive"))
      (node (ref "L3") (pin "2") (pinfunction "2_2") (pintype "passive"))
      (node (ref "R4") (pin "1") (pinfunction "1_1") (pintype "passive"))
    )
    (net (code "34") (name "Net-(C23-Pad1)") (class "Default")
      (node (ref "C23") (pin "1") (pinfunction "1_1") (pintype "passive"))
      (node (ref "L5") (pin "2") (pinfunction "2_2") (pintype "passive"))
    )
    (net (code "35") (name "Net-(IC1-AIN0{slash}REFP1)") (class "Default")
      (node (ref "C24") (pin "1") (pinfunction "1_1") (pintype "passive"))
      (node (ref "IC1") (pin "9") (pinfunction "AIN0/REFP1_9") (pintype "passive"))
      (node (ref "R7") (pin "2") (pinfunction "2_2") (pintype "passive"))
    )
    (net (code "36") (name "Net-(IC1-AIN1)") (class "Default")
      (node (ref "C25") (pin "1") (pinfunction "1_1") (pintype "passive"))
      (node (ref "IC1") (pin "8") (pinfunction "AIN1_8") (pintype "passive"))
      (node (ref "R8") (pin "2") (pinfunction "2_2") (pintype "passive"))
    )
    (net (code "37") (name "Net-(IC1-AIN2)") (class "Default")
      (node (ref "C26") (pin "1") (pinfunction "1_1") (pintype "passive"))
      (node (ref "IC1") (pin "5") (pinfunction "AIN2_5") (pintype "passive"))
      (node (ref "R9") (pin "2") (pinfunction "2_2") (pintype "passive"))
    )
    (net (code "38") (name "Net-(IC1-AIN3{slash}REFN1)") (class "Default")
      (node (ref "C27") (pin "1") (pinfunction "1_1") (pintype "passive"))
      (node (ref "IC1") (pin "4") (pinfunction "AIN3/REFN1_4") (pintype "passive"))
      (node (ref "R10") (pin "2") (pinfunction "2_2") (pintype "passive"))
    )
    (net (code "39") (name "Net-(IC1-AVDD)") (class "Default")
      (node (ref "C2") (pin "1") (pinfunction "1_1") (pintype "passive"))
      (node (ref "C3") (pin "1") (pinfunction "1_1") (pintype "passive"))
      (node (ref "FB1") (pin "1") (pinfunction "1_1") (pintype "passive"))
      (node (ref "IC1") (pin "10") (pinfunction "AVDD_10") (pintype "passive"))
    )
    (net (code "40") (name "Net-(IC3-PB2)") (class "Default")
      (node (ref "IC3") (pin "32") (pinfunction "PB2_32") (pintype "passive"))
      (node (ref "R3") (pin "2") (pinfunction "2_2") (pintype "passive"))
    )
    (net (code "41") (name "Net-(IC3-PB14)") (class "Default")
      (node (ref "IC3") (pin "12") (pinfunction "PB14_12") (pintype "passive"))
      (node (ref "LED2") (pin "1") (pinfunction "K_1") (pintype "passive"))
    )
    (net (code "42") (name "Net-(IC3-VCAP)") (class "Default")
      (node (ref "C12") (pin "1") (pinfunction "1_1") (pintype "passive"))
      (node (ref "IC3") (pin "29") (pinfunction "VCAP_29") (pintype "passive"))
    )
    (net (code "43") (name "Net-(LED1-K)") (class "Default")
      (node (ref "LED1") (pin "1") (pinfunction "K_1") (pintype "passive"))
      (node (ref "R11") (pin "1") (pinfunction "1_1") (pintype "passive"))
    )
    (net (code "44") (name "Net-(LED2-A)") (class "Default")
      (node (ref "LED2") (pin "2") (pinfunction "A_2") (pintype "passive"))
      (node (ref "R12") (pin "1") (pinfunction "1_1") (pintype "passive"))
    )
    (net (code "45") (name "unconnected-(AC1-OCS_AUX-Pad10)") (class "Default")
      (node (ref "AC1") (pin "10") (pinfunction "OCS_AUX_10") (pintype "passive"))
    )
    (net (code "46") (name "unconnected-(AC1-SCX-Pad3)") (class "Default")
      (node (ref "AC1") (pin "3") (pinfunction "SCX_3") (pintype "passive+no_connect"))
    )
    (net (code "47") (name "unconnected-(AC1-SDO_AUX-Pad11)") (class "Default")
      (node (ref "AC1") (pin "11") (pinfunction "SDO_AUX_11") (pintype "passive"))
    )
    (net (code "48") (name "unconnected-(AC1-SDX-Pad2)") (class "Default")
      (node (ref "AC1") (pin "2") (pinfunction "SDX_2") (pintype "passive+no_connect"))
    )
    (net (code "49") (name "unconnected-(IC1-REFN0-Pad6)") (class "Default")
      (node (ref "IC1") (pin "6") (pinfunction "REFN0_6") (pintype "passive"))
    )
    (net (code "50") (name "unconnected-(IC1-REFP0-Pad7)") (class "Default")
      (node (ref "IC1") (pin "7") (pinfunction "REFP0_7") (pintype "passive"))
    )
    (net (code "51") (name "unconnected-(IC3-LPAWUR-Pad14)") (class "Default")
      (node (ref "IC3") (pin "14") (pinfunction "LPAWUR_14") (pintype "passive"))
    )
    (net (code "52") (name "unconnected-(IC3-PB7-Pad23)") (class "Default")
      (node (ref "IC3") (pin "23") (pinfunction "PB7_23") (pintype "passive"))
    )
    (net (code "53") (name "unconnected-(IC3-PB15-Pad13)") (class "Default")
      (node (ref "IC3") (pin "13") (pinfunction "PB15_13") (pintype "passive"))
    )
    (net (code "54") (name "unconnected-(IC3-TX-Pad18)") (class "Default")
      (node (ref "IC3") (pin "18") (pinfunction "TX_18") (pintype "passive"))
    )
  )
)
